# ELEKTRA-PMIC_v0_4-35X22_86.net
KiCad netlist of a schematic drawn in EAGLE
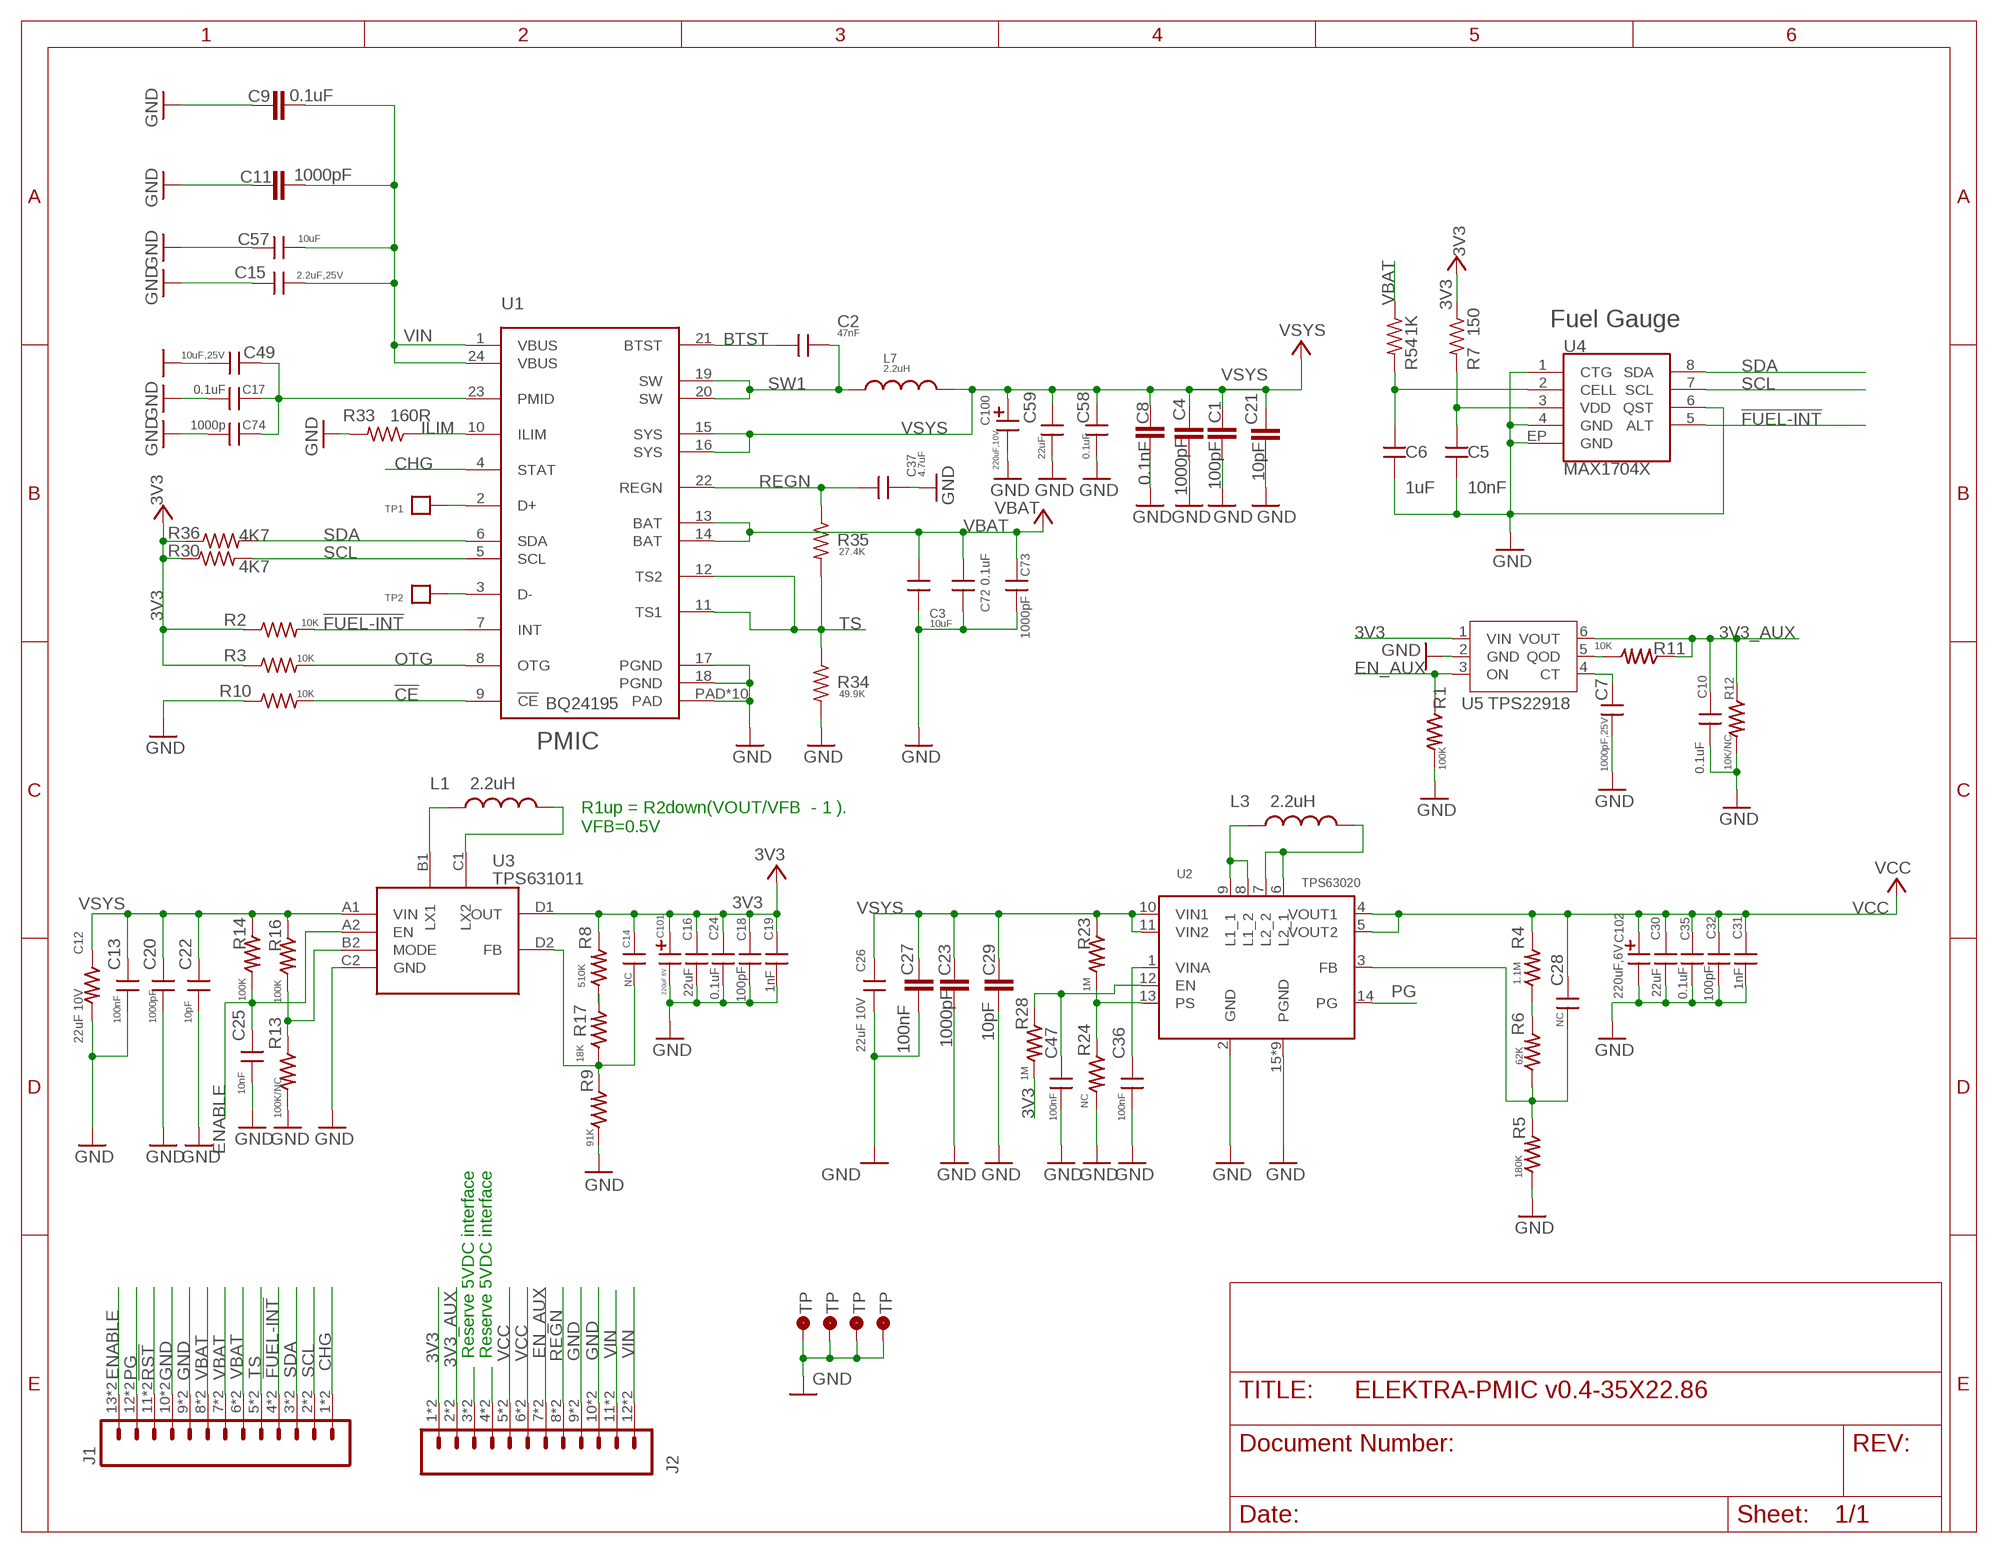
[diagram p0: schematic, sheet 1]

(export (version "E")
  (design (tool "Eeschema 10.0.6"))
  (components
    (comp (ref "C1")
      (value "100pF")
      (footprint "eagle-import:C0402_B")
      (libsource (lib "eagle-import") (part "CAP_1"))
    )
    (comp (ref "C2")
      (value "47nF")
      (footprint "eagle-import:C-0402")
      (libsource (lib "eagle-import") (part "particle SZ_CAP0402"))
    )
    (comp (ref "C3")
      (value "10uF")
      (footprint "eagle-import:C0805")
      (libsource (lib "eagle-import") (part "particle SZ_CAPC0805"))
    )
    (comp (ref "C4")
      (value "1000pF")
      (footprint "eagle-import:C0402_B")
      (libsource (lib "eagle-import") (part "CAP_1"))
    )
    (comp (ref "C5")
      (value "10nF")
      (footprint "eagle-import:C0402")
      (libsource (lib "eagle-import") (part "particle SZ_CAP0402A"))
    )
    (comp (ref "C6")
      (value "1uF")
      (footprint "eagle-import:C0402")
      (libsource (lib "eagle-import") (part "particle SZ_CAP0402A"))
    )
    (comp (ref "C7")
      (value "1000pF,25V")
      (footprint "eagle-import:C0402")
      (libsource (lib "eagle-import") (part "particle SZ_CAP0402A"))
    )
    (comp (ref "C8")
      (value "0.1nF")
      (footprint "eagle-import:C0402_B")
      (libsource (lib "eagle-import") (part "CAP_1"))
    )
    (comp (ref "C9")
      (value "0.1uF")
      (footprint "eagle-import:C0402_B")
      (libsource (lib "eagle-import") (part "CAP_1"))
    )
    (comp (ref "C10")
      (value "0.1uF")
      (footprint "eagle-import:C0201-N")
      (libsource (lib "eagle-import") (part "CAPC0201-N"))
    )
    (comp (ref "C11")
      (value "1000pF")
      (footprint "eagle-import:C0402_B")
      (libsource (lib "eagle-import") (part "CAP_1"))
    )
    (comp (ref "C12")
      (value "22uF 10V")
      (footprint "eagle-import:R-0603A")
      (libsource (lib "eagle-import") (part "RESR0603A"))
    )
    (comp (ref "C13")
      (value "100nF")
      (footprint "eagle-import:C0201-N")
      (libsource (lib "eagle-import") (part "CAPC0201-N"))
    )
    (comp (ref "C14")
      (value "NC")
      (footprint "eagle-import:C0201-N")
      (libsource (lib "eagle-import") (part "CAPC0201-N"))
    )
    (comp (ref "C15")
      (value "2.2uF,25V")
      (footprint "eagle-import:C-0603A")
      (libsource (lib "eagle-import") (part "particle SZ_CAP0603A"))
    )
    (comp (ref "C16")
      (value "22uF")
      (footprint "eagle-import:C-0603A")
      (libsource (lib "eagle-import") (part "particle SZ_21650216_CAP0603A"))
    )
    (comp (ref "C17")
      (value "0.1uF")
      (footprint "eagle-import:C0402")
      (libsource (lib "eagle-import") (part "CAP0402A"))
    )
    (comp (ref "C18")
      (value "100pF")
      (footprint "eagle-import:C0402")
      (libsource (lib "eagle-import") (part "particle SZ_CAP0402A"))
    )
    (comp (ref "C19")
      (value "1nF")
      (footprint "eagle-import:C0402")
      (libsource (lib "eagle-import") (part "particle SZ_CAP0402A"))
    )
    (comp (ref "C20")
      (value "1000pF")
      (footprint "eagle-import:C0201-N")
      (libsource (lib "eagle-import") (part "CAPC0201-N"))
    )
    (comp (ref "C21")
      (value "10pF")
      (footprint "eagle-import:C0402_B")
      (libsource (lib "eagle-import") (part "CAP_1"))
    )
    (comp (ref "C22")
      (value "10pF")
      (footprint "eagle-import:C0201-N")
      (libsource (lib "eagle-import") (part "CAPC0201-N"))
    )
    (comp (ref "C23")
      (value "1000pF")
      (footprint "eagle-import:C0402_B")
      (libsource (lib "eagle-import") (part "CAP_1"))
    )
    (comp (ref "C24")
      (value "0.1uF")
      (footprint "eagle-import:C0402")
      (libsource (lib "eagle-import") (part "particle SZ_CAP0402A"))
    )
    (comp (ref "C25")
      (value "10nF")
      (footprint "eagle-import:C0201-N")
      (libsource (lib "eagle-import") (part "CAPC0201-N"))
    )
    (comp (ref "C26")
      (value "22uF 10V")
      (footprint "eagle-import:C0603")
      (libsource (lib "eagle-import") (part "particle SZ_21650216_CAPC0603"))
    )
    (comp (ref "C27")
      (value "100nF")
      (footprint "eagle-import:C0402_B")
      (libsource (lib "eagle-import") (part "CAP_1"))
    )
    (comp (ref "C28")
      (value "NC")
      (footprint "eagle-import:C0201-N")
      (libsource (lib "eagle-import") (part "CAPC0201-N"))
    )
    (comp (ref "C29")
      (value "10pF")
      (footprint "eagle-import:C0402_B")
      (libsource (lib "eagle-import") (part "CAP_1"))
    )
    (comp (ref "C30")
      (value "22uF")
      (footprint "eagle-import:C-0603A")
      (libsource (lib "eagle-import") (part "particle SZ_21650216_CAP0603A"))
    )
    (comp (ref "C31")
      (value "1nF")
      (footprint "eagle-import:C0402")
      (libsource (lib "eagle-import") (part "particle SZ_CAP0402A"))
    )
    (comp (ref "C32")
      (value "100pF")
      (footprint "eagle-import:C0402")
      (libsource (lib "eagle-import") (part "particle SZ_CAP0402A"))
    )
    (comp (ref "C35")
      (value "0.1uF")
      (footprint "eagle-import:C0402")
      (libsource (lib "eagle-import") (part "particle SZ_CAP0402A"))
    )
    (comp (ref "C36")
      (value "100nF")
      (footprint "eagle-import:C0201-N")
      (libsource (lib "eagle-import") (part "CAPC0201-N"))
    )
    (comp (ref "C37")
      (value "4.7uF")
      (footprint "eagle-import:C0402")
      (libsource (lib "eagle-import") (part "particle SZ_CAP0402A"))
    )
    (comp (ref "C47")
      (value "100nF")
      (footprint "eagle-import:C0201-N")
      (libsource (lib "eagle-import") (part "CAPC0201-N"))
    )
    (comp (ref "C49")
      (value "10uF,25V")
      (footprint "eagle-import:C-0603A")
      (libsource (lib "eagle-import") (part "particle SZ_CAP0603A"))
    )
    (comp (ref "C57")
      (value "10uF")
      (footprint "eagle-import:C-0603A")
      (libsource (lib "eagle-import") (part "particle SZ_CAP0603A"))
    )
    (comp (ref "C58")
      (value "0.1uF")
      (footprint "eagle-import:C0402")
      (libsource (lib "eagle-import") (part "particle SZ_CAP0402A"))
    )
    (comp (ref "C59")
      (value "22uF")
      (footprint "eagle-import:C0603")
      (libsource (lib "eagle-import") (part "particle SZ_CAPC0603"))
    )
    (comp (ref "C72")
      (value "0.1uF")
      (footprint "eagle-import:C-0402")
      (libsource (lib "eagle-import") (part "particle SZ_CAP0402"))
    )
    (comp (ref "C73")
      (value "1000pF")
      (footprint "eagle-import:C-0402")
      (libsource (lib "eagle-import") (part "particle SZ_CAP0402"))
    )
    (comp (ref "C74")
      (value "1000p")
      (footprint "eagle-import:C-0402")
      (libsource (lib "eagle-import") (part "particle SZ_CAP0402"))
    )
    (comp (ref "C100")
      (value "220uF,10V")
      (footprint "eagle-import:CASE-B")
      (libsource (lib "eagle-import") (part "CAP-ECASE_B"))
    )
    (comp (ref "C101")
      (value "220uF.6V")
      (footprint "eagle-import:CASE-B")
      (libsource (lib "eagle-import") (part "CAP-ECASE_B"))
    )
    (comp (ref "C102")
      (value "220uF,6V")
      (footprint "eagle-import:CASE-B")
      (libsource (lib "eagle-import") (part "CAP-ECASE_B"))
    )
    (comp (ref "J1")
      (value "M13PTH-CST-R")
      (footprint "eagle-import:1X13-CASTELLATED")
      (libsource (lib "eagle-import") (part "M13PTH-CST-R"))
    )
    (comp (ref "J2")
      (value "M12PTH-CST-R")
      (footprint "eagle-import:1X12-CASTELLATED")
      (libsource (lib "eagle-import") (part "M12PTH-CST-R"))
    )
    (comp (ref "L1")
      (value "2.2uH")
      (footprint "eagle-import:INDUCTOR-2520")
      (libsource (lib "eagle-import") (part "INDUCTOR-SPARKFUNINDUCTOR-2520"))
    )
    (comp (ref "L3")
      (value "2.2uH")
      (footprint "eagle-import:INDUCTOR-2520")
      (libsource (lib "eagle-import") (part "INDUCTOR-SPARKFUNINDUCTOR-2520"))
    )
    (comp (ref "L7")
      (value "2.2uH")
      (footprint "eagle-import:INDUCTOR-4040")
      (libsource (lib "eagle-import") (part "INDUCTORI"))
    )
    (comp (ref "R1")
      (value "100K")
      (footprint "eagle-import:R0201-N")
      (libsource (lib "eagle-import") (part "RESR0201-N"))
    )
    (comp (ref "R2")
      (value "10K")
      (footprint "eagle-import:R0402_B")
      (libsource (lib "eagle-import") (part "Spark_R-US_"))
    )
    (comp (ref "R3")
      (value "10K")
      (footprint "eagle-import:R0402_B")
      (libsource (lib "eagle-import") (part "Spark_R-US_"))
    )
    (comp (ref "R4")
      (value "1.1M")
      (footprint "eagle-import:R0201-N")
      (libsource (lib "eagle-import") (part "RESR0201-N"))
    )
    (comp (ref "R5")
      (value "180K")
      (footprint "eagle-import:R0201-N")
      (libsource (lib "eagle-import") (part "RESR0201-N"))
    )
    (comp (ref "R6")
      (value "62K")
      (footprint "eagle-import:R0201-N")
      (libsource (lib "eagle-import") (part "RESR0201-N"))
    )
    (comp (ref "R7")
      (value "150")
      (footprint "eagle-import:R0402_B")
      (libsource (lib "eagle-import") (part "R-US_"))
    )
    (comp (ref "R8")
      (value "510K")
      (footprint "eagle-import:R0201-N")
      (libsource (lib "eagle-import") (part "RESR0201-N"))
    )
    (comp (ref "R9")
      (value "91K")
      (footprint "eagle-import:R0201-N")
      (libsource (lib "eagle-import") (part "RESR0201-N"))
    )
    (comp (ref "R10")
      (value "10K")
      (footprint "eagle-import:R0402_B")
      (libsource (lib "eagle-import") (part "Spark_R-US_"))
    )
    (comp (ref "R11")
      (value "10K")
      (footprint "eagle-import:R0201-N")
      (libsource (lib "eagle-import") (part "RESR0201-N"))
    )
    (comp (ref "R12")
      (value "10K/NC")
      (footprint "eagle-import:R0201-N")
      (libsource (lib "eagle-import") (part "RESR0201-N"))
    )
    (comp (ref "R13")
      (value "100K/NC")
      (footprint "eagle-import:R0201-N")
      (libsource (lib "eagle-import") (part "RESR0201-N"))
    )
    (comp (ref "R14")
      (value "100K")
      (footprint "eagle-import:R0201-N")
      (libsource (lib "eagle-import") (part "RESR0201-N"))
    )
    (comp (ref "R16")
      (value "100K")
      (footprint "eagle-import:R0201-N")
      (libsource (lib "eagle-import") (part "RESR0201-N"))
    )
    (comp (ref "R17")
      (value "18K")
      (footprint "eagle-import:R0201-N")
      (libsource (lib "eagle-import") (part "RESR0201-N"))
    )
    (comp (ref "R23")
      (value "1M")
      (footprint "eagle-import:R0201-N")
      (libsource (lib "eagle-import") (part "RESR0201-N"))
    )
    (comp (ref "R24")
      (value "NC")
      (footprint "eagle-import:R0201-N")
      (libsource (lib "eagle-import") (part "RESR0201-N"))
    )
    (comp (ref "R28")
      (value "1M")
      (footprint "eagle-import:R0201-N")
      (libsource (lib "eagle-import") (part "RESR0201-N"))
    )
    (comp (ref "R30")
      (value "4K7")
      (footprint "eagle-import:R0402_B")
      (libsource (lib "eagle-import") (part "R-US_"))
    )
    (comp (ref "R33")
      (value "160R")
      (footprint "eagle-import:R0402_B")
      (libsource (lib "eagle-import") (part "R-US_"))
    )
    (comp (ref "R34")
      (value "49.9K")
      (footprint "eagle-import:R0402_B")
      (libsource (lib "eagle-import") (part "Spark_R-US_"))
    )
    (comp (ref "R35")
      (value "27.4K")
      (footprint "eagle-import:R0402_B")
      (libsource (lib "eagle-import") (part "Spark_R-US_"))
    )
    (comp (ref "R36")
      (value "4K7")
      (footprint "eagle-import:R0402_B")
      (libsource (lib "eagle-import") (part "R-US_"))
    )
    (comp (ref "R54")
      (value "1K")
      (footprint "eagle-import:R0402_B")
      (libsource (lib "eagle-import") (part "R-US_"))
    )
    (comp (ref "TP1")
      (value "TP1311MM")
      (footprint "eagle-import:TP-1311MM")
      (libsource (lib "eagle-import") (part "TP1311MM"))
    )
    (comp (ref "TP2")
      (value "TP1311MM")
      (footprint "eagle-import:TP-1311MM")
      (libsource (lib "eagle-import") (part "TP1311MM"))
    )
    (comp (ref "U$1")
      (value "TP")
      (footprint "eagle-import:TP_2.33X1.37")
      (libsource (lib "eagle-import") (part "TP"))
    )
    (comp (ref "U$2")
      (value "TP")
      (footprint "eagle-import:TP_2.33X1.37")
      (libsource (lib "eagle-import") (part "TP"))
    )
    (comp (ref "U$4")
      (value "TP")
      (footprint "eagle-import:TP_2.33X1.37")
      (libsource (lib "eagle-import") (part "TP"))
    )
    (comp (ref "U$5")
      (value "TP")
      (footprint "eagle-import:TP_2.33X1.37")
      (libsource (lib "eagle-import") (part "TP"))
    )
    (comp (ref "U1")
      (value "BQ24195")
      (footprint "eagle-import:ELECTRON_QFN24")
      (libsource (lib "eagle-import") (part "ELECTRON_BQ24298RTWR"))
    )
    (comp (ref "U2")
      (value "TPS63020")
      (footprint "eagle-import:TPS63020")
      (libsource (lib "eagle-import") (part "TPS63020"))
    )
    (comp (ref "U3")
      (value "TPS631011")
      (footprint "eagle-import:DSBGA")
      (libsource (lib "eagle-import") (part "TPS631010"))
    )
    (comp (ref "U4")
      (value "MAX1704X")
      (footprint "eagle-import:TDFN-8")
      (libsource (lib "eagle-import") (part "MAX1704X"))
    )
    (comp (ref "U5")
      (value "TPS22918")
      (footprint "eagle-import:SOT-23-6")
      (libsource (lib "eagle-import") (part "TPS22918"))
    )
  )
  (nets
    (net (code "1") (name "/3V3_AUX") (class "Default")
      (node (ref "C10") (pin "1") (pinfunction "1_1") (pintype "bidirectional"))
      (node (ref "J2") (pin "2") (pinfunction "2_2") (pintype "passive"))
      (node (ref "J2") (pin "@2") (pinfunction "2_@2") (pintype "passive"))
      (node (ref "R11") (pin "1") (pinfunction "1_1") (pintype "bidirectional"))
      (node (ref "R12") (pin "1") (pinfunction "1_1") (pintype "bidirectional"))
      (node (ref "U5") (pin "6") (pinfunction "VOUT_6") (pintype "bidirectional"))
    )
    (net (code "2") (name "/BTST") (class "Default")
      (node (ref "C2") (pin "1") (pinfunction "1_1") (pintype "bidirectional"))
      (node (ref "U1") (pin "21") (pinfunction "BTST_21") (pintype "bidirectional"))
    )
    (net (code "3") (name "/CHG") (class "Default")
      (node (ref "J1") (pin "1") (pinfunction "1_1") (pintype "passive"))
      (node (ref "J1") (pin "@1") (pinfunction "1_@1") (pintype "passive"))
      (node (ref "U1") (pin "4") (pinfunction "STAT_4") (pintype "bidirectional"))
    )
    (net (code "4") (name "/ENABLE") (class "Default")
      (node (ref "C25") (pin "1") (pinfunction "1_1") (pintype "bidirectional"))
      (node (ref "J1") (pin "13") (pinfunction "13_13") (pintype "passive"))
      (node (ref "J1") (pin "@13") (pinfunction "13_@13") (pintype "passive"))
      (node (ref "R14") (pin "2") (pinfunction "2_2") (pintype "bidirectional"))
      (node (ref "U3") (pin "A2") (pinfunction "EN_A2") (pintype "bidirectional"))
    )
    (net (code "5") (name "/EN_AUX") (class "Default")
      (node (ref "J2") (pin "7") (pinfunction "7_7") (pintype "passive"))
      (node (ref "J2") (pin "@7") (pinfunction "7_@7") (pintype "passive"))
      (node (ref "R1") (pin "1") (pinfunction "1_1") (pintype "bidirectional"))
      (node (ref "U5") (pin "3") (pinfunction "ON_3") (pintype "bidirectional"))
    )
    (net (code "6") (name "/ILIM") (class "Default")
      (node (ref "R33") (pin "1") (pinfunction "1_1") (pintype "passive"))
      (node (ref "U1") (pin "10") (pinfunction "ILIM_10") (pintype "output"))
    )
    (net (code "7") (name "/OTG") (class "Default")
      (node (ref "R3") (pin "2") (pinfunction "2_2") (pintype "passive"))
      (node (ref "U1") (pin "8") (pinfunction "OTG_8") (pintype "bidirectional"))
    )
    (net (code "8") (name "/PG") (class "Default")
      (node (ref "J1") (pin "12") (pinfunction "12_12") (pintype "passive"))
      (node (ref "J1") (pin "@12") (pinfunction "12_@12") (pintype "passive"))
      (node (ref "U2") (pin "14") (pinfunction "PG_14") (pintype "bidirectional"))
    )
    (net (code "9") (name "/REGN") (class "Default")
      (node (ref "C37") (pin "1") (pinfunction "1_1") (pintype "bidirectional"))
      (node (ref "J2") (pin "8") (pinfunction "8_8") (pintype "passive"))
      (node (ref "J2") (pin "@8") (pinfunction "8_@8") (pintype "passive"))
      (node (ref "R35") (pin "1") (pinfunction "1_1") (pintype "passive"))
      (node (ref "U1") (pin "22") (pinfunction "REGN_22") (pintype "bidirectional"))
    )
    (net (code "10") (name "/SCL") (class "Default")
      (node (ref "J1") (pin "2") (pinfunction "2_2") (pintype "passive"))
      (node (ref "J1") (pin "@2") (pinfunction "2_@2") (pintype "passive"))
      (node (ref "R30") (pin "2") (pinfunction "2_2") (pintype "passive"))
      (node (ref "U1") (pin "5") (pinfunction "SCL_5") (pintype "output"))
      (node (ref "U4") (pin "7") (pinfunction "SCL_7") (pintype "bidirectional"))
    )
    (net (code "11") (name "/SDA") (class "Default")
      (node (ref "J1") (pin "3") (pinfunction "3_3") (pintype "passive"))
      (node (ref "J1") (pin "@3") (pinfunction "3_@3") (pintype "passive"))
      (node (ref "R36") (pin "2") (pinfunction "2_2") (pintype "passive"))
      (node (ref "U1") (pin "6") (pinfunction "SDA_6") (pintype "bidirectional"))
      (node (ref "U4") (pin "8") (pinfunction "SDA_8") (pintype "bidirectional"))
    )
    (net (code "12") (name "/SW1") (class "Default")
      (node (ref "C2") (pin "2") (pinfunction "2_2") (pintype "bidirectional"))
      (node (ref "L7") (pin "P$1") (pinfunction "1_P$1") (pintype "passive"))
      (node (ref "U1") (pin "19") (pinfunction "SW_19") (pintype "power_in"))
      (node (ref "U1") (pin "20") (pinfunction "SW_20") (pintype "power_in"))
    )
    (net (code "13") (name "/TS") (class "Default")
      (node (ref "J1") (pin "5") (pinfunction "5_5") (pintype "passive"))
      (node (ref "J1") (pin "@5") (pinfunction "5_@5") (pintype "passive"))
      (node (ref "R34") (pin "1") (pinfunction "1_1") (pintype "passive"))
      (node (ref "R35") (pin "2") (pinfunction "2_2") (pintype "passive"))
      (node (ref "U1") (pin "11") (pinfunction "TS1_11") (pintype "bidirectional"))
      (node (ref "U1") (pin "12") (pinfunction "TS2_12") (pintype "bidirectional"))
    )
    (net (code "14") (name "/VIN") (class "Default")
      (node (ref "C11") (pin "2") (pinfunction "P$2_2") (pintype "passive"))
      (node (ref "C15") (pin "1") (pinfunction "1_1") (pintype "bidirectional"))
      (node (ref "C57") (pin "1") (pinfunction "1_1") (pintype "bidirectional"))
      (node (ref "C9") (pin "2") (pinfunction "P$2_2") (pintype "passive"))
      (node (ref "J2") (pin "11") (pinfunction "11_11") (pintype "passive"))
      (node (ref "J2") (pin "12") (pinfunction "12_12") (pintype "passive"))
      (node (ref "J2") (pin "@11") (pinfunction "11_@11") (pintype "passive"))
      (node (ref "J2") (pin "@12") (pinfunction "12_@12") (pintype "passive"))
      (node (ref "U1") (pin "1") (pinfunction "VBUS_1") (pintype "power_in"))
      (node (ref "U1") (pin "24") (pinfunction "VBUS_24") (pintype "passive"))
    )
    (net (code "15") (name "/~{CE}") (class "Default")
      (node (ref "R10") (pin "2") (pinfunction "2_2") (pintype "passive"))
      (node (ref "U1") (pin "9") (pinfunction "~{CE}_9") (pintype "output"))
    )
    (net (code "16") (name "/~{FUEL-INT}") (class "Default")
      (node (ref "J1") (pin "4") (pinfunction "4_4") (pintype "passive"))
      (node (ref "J1") (pin "@4") (pinfunction "4_@4") (pintype "passive"))
      (node (ref "R2") (pin "2") (pinfunction "2_2") (pintype "passive"))
      (node (ref "U1") (pin "7") (pinfunction "INT_7") (pintype "bidirectional"))
      (node (ref "U4") (pin "5") (pinfunction "ALT_5") (pintype "bidirectional"))
    )
    (net (code "17") (name "/~{RST}") (class "Default")
      (node (ref "J1") (pin "11") (pinfunction "11_11") (pintype "passive"))
      (node (ref "J1") (pin "@11") (pinfunction "11_@11") (pintype "passive"))
    )
    (net (code "18") (name "3V3") (class "Default")
      (node (ref "C101") (pin "P$1") (pinfunction "1_P$1") (pintype "bidirectional"))
      (node (ref "C14") (pin "1") (pinfunction "1_1") (pintype "bidirectional"))
      (node (ref "C16") (pin "1") (pinfunction "1_1") (pintype "bidirectional"))
      (node (ref "C18") (pin "1") (pinfunction "1_1") (pintype "bidirectional"))
      (node (ref "C19") (pin "1") (pinfunction "1_1") (pintype "bidirectional"))
      (node (ref "C24") (pin "1") (pinfunction "1_1") (pintype "bidirectional"))
      (node (ref "J2") (pin "1") (pinfunction "1_1") (pintype "passive"))
      (node (ref "J2") (pin "@1") (pinfunction "1_@1") (pintype "passive"))
      (node (ref "R2") (pin "1") (pinfunction "1_1") (pintype "passive"))
      (node (ref "R28") (pin "2") (pinfunction "2_2") (pintype "bidirectional"))
      (node (ref "R3") (pin "1") (pinfunction "1_1") (pintype "passive"))
      (node (ref "R30") (pin "1") (pinfunction "1_1") (pintype "passive"))
      (node (ref "R36") (pin "1") (pinfunction "1_1") (pintype "passive"))
      (node (ref "R7") (pin "1") (pinfunction "1_1") (pintype "passive"))
      (node (ref "R8") (pin "2") (pinfunction "2_2") (pintype "bidirectional"))
      (node (ref "U3") (pin "D1") (pinfunction "OUT_D1") (pintype "bidirectional"))
      (node (ref "U5") (pin "1") (pinfunction "VIN_1") (pintype "bidirectional"))
    )
    (net (code "19") (name "GND") (class "Default")
      (node (ref "C1") (pin "1") (pinfunction "P$1_1") (pintype "passive"))
      (node (ref "C10") (pin "2") (pinfunction "2_2") (pintype "bidirectional"))
      (node (ref "C100") (pin "P$2") (pinfunction "2_P$2") (pintype "bidirectional"))
      (node (ref "C101") (pin "P$2") (pinfunction "2_P$2") (pintype "bidirectional"))
      (node (ref "C102") (pin "P$2") (pinfunction "2_P$2") (pintype "bidirectional"))
      (node (ref "C11") (pin "1") (pinfunction "P$1_1") (pintype "passive"))
      (node (ref "C12") (pin "2") (pinfunction "2_2") (pintype "bidirectional"))
      (node (ref "C13") (pin "2") (pinfunction "2_2") (pintype "bidirectional"))
      (node (ref "C15") (pin "2") (pinfunction "2_2") (pintype "bidirectional"))
      (node (ref "C16") (pin "2") (pinfunction "2_2") (pintype "bidirectional"))
      (node (ref "C17") (pin "1") (pinfunction "1_1") (pintype "bidirectional"))
      (node (ref "C18") (pin "2") (pinfunction "2_2") (pintype "bidirectional"))
      (node (ref "C19") (pin "2") (pinfunction "2_2") (pintype "bidirectional"))
      (node (ref "C20") (pin "2") (pinfunction "2_2") (pintype "bidirectional"))
      (node (ref "C21") (pin "1") (pinfunction "P$1_1") (pintype "passive"))
      (node (ref "C22") (pin "2") (pinfunction "2_2") (pintype "bidirectional"))
      (node (ref "C23") (pin "1") (pinfunction "P$1_1") (pintype "passive"))
      (node (ref "C24") (pin "2") (pinfunction "2_2") (pintype "bidirectional"))
      (node (ref "C25") (pin "2") (pinfunction "2_2") (pintype "bidirectional"))
      (node (ref "C26") (pin "2") (pinfunction "2_2") (pintype "bidirectional"))
      (node (ref "C27") (pin "1") (pinfunction "P$1_1") (pintype "passive"))
      (node (ref "C29") (pin "1") (pinfunction "P$1_1") (pintype "passive"))
      (node (ref "C3") (pin "2") (pinfunction "2_2") (pintype "bidirectional"))
      (node (ref "C30") (pin "2") (pinfunction "2_2") (pintype "bidirectional"))
      (node (ref "C31") (pin "2") (pinfunction "2_2") (pintype "bidirectional"))
      (node (ref "C32") (pin "2") (pinfunction "2_2") (pintype "bidirectional"))
      (node (ref "C35") (pin "2") (pinfunction "2_2") (pintype "bidirectional"))
      (node (ref "C36") (pin "2") (pinfunction "2_2") (pintype "bidirectional"))
      (node (ref "C37") (pin "2") (pinfunction "2_2") (pintype "bidirectional"))
      (node (ref "C4") (pin "1") (pinfunction "P$1_1") (pintype "passive"))
      (node (ref "C47") (pin "2") (pinfunction "2_2") (pintype "bidirectional"))
      (node (ref "C49") (pin "2") (pinfunction "2_2") (pintype "bidirectional"))
      (node (ref "C5") (pin "2") (pinfunction "2_2") (pintype "bidirectional"))
      (node (ref "C57") (pin "2") (pinfunction "2_2") (pintype "bidirectional"))
      (node (ref "C58") (pin "2") (pinfunction "2_2") (pintype "bidirectional"))
      (node (ref "C59") (pin "2") (pinfunction "2_2") (pintype "bidirectional"))
      (node (ref "C6") (pin "2") (pinfunction "2_2") (pintype "bidirectional"))
      (node (ref "C7") (pin "2") (pinfunction "2_2") (pintype "bidirectional"))
      (node (ref "C72") (pin "2") (pinfunction "2_2") (pintype "bidirectional"))
      (node (ref "C73") (pin "2") (pinfunction "2_2") (pintype "bidirectional"))
      (node (ref "C74") (pin "1") (pinfunction "1_1") (pintype "bidirectional"))
      (node (ref "C8") (pin "1") (pinfunction "P$1_1") (pintype "passive"))
      (node (ref "C9") (pin "1") (pinfunction "P$1_1") (pintype "passive"))
      (node (ref "J1") (pin "10") (pinfunction "10_10") (pintype "passive"))
      (node (ref "J1") (pin "9") (pinfunction "9_9") (pintype "passive"))
      (node (ref "J1") (pin "@10") (pinfunction "10_@10") (pintype "passive"))
      (node (ref "J1") (pin "@9") (pinfunction "9_@9") (pintype "passive"))
      (node (ref "J2") (pin "10") (pinfunction "10_10") (pintype "passive"))
      (node (ref "J2") (pin "9") (pinfunction "9_9") (pintype "passive"))
      (node (ref "J2") (pin "@10") (pinfunction "10_@10") (pintype "passive"))
      (node (ref "J2") (pin "@9") (pinfunction "9_@9") (pintype "passive"))
      (node (ref "R1") (pin "2") (pinfunction "2_2") (pintype "bidirectional"))
      (node (ref "R10") (pin "1") (pinfunction "1_1") (pintype "passive"))
      (node (ref "R12") (pin "2") (pinfunction "2_2") (pintype "bidirectional"))
      (node (ref "R13") (pin "2") (pinfunction "2_2") (pintype "bidirectional"))
      (node (ref "R24") (pin "2") (pinfunction "2_2") (pintype "bidirectional"))
      (node (ref "R33") (pin "2") (pinfunction "2_2") (pintype "passive"))
      (node (ref "R34") (pin "2") (pinfunction "2_2") (pintype "passive"))
      (node (ref "R5") (pin "1") (pinfunction "1_1") (pintype "bidirectional"))
      (node (ref "R9") (pin "1") (pinfunction "1_1") (pintype "bidirectional"))
      (node (ref "U$1") (pin "1") (pinfunction "TP_1") (pintype "bidirectional"))
      (node (ref "U$2") (pin "1") (pinfunction "TP_1") (pintype "bidirectional"))
      (node (ref "U$4") (pin "1") (pinfunction "TP_1") (pintype "bidirectional"))
      (node (ref "U$5") (pin "1") (pinfunction "TP_1") (pintype "bidirectional"))
      (node (ref "U1") (pin "17") (pinfunction "PGND_17") (pintype "passive"))
      (node (ref "U1") (pin "18") (pinfunction "PGND_18") (pintype "passive"))
      (node (ref "U1") (pin "PAD") (pinfunction "PAD_PAD") (pintype "power_in"))
      (node (ref "U1") (pin "PAD@1") (pinfunction "PAD_PAD@1") (pintype "power_in"))
      (node (ref "U1") (pin "PAD@2") (pinfunction "PAD_PAD@2") (pintype "power_in"))
      (node (ref "U1") (pin "PAD@3") (pinfunction "PAD_PAD@3") (pintype "power_in"))
      (node (ref "U1") (pin "PAD@4") (pinfunction "PAD_PAD@4") (pintype "power_in"))
      (node (ref "U1") (pin "PAD@5") (pinfunction "PAD_PAD@5") (pintype "power_in"))
      (node (ref "U1") (pin "PAD@6") (pinfunction "PAD_PAD@6") (pintype "power_in"))
      (node (ref "U1") (pin "PAD@7") (pinfunction "PAD_PAD@7") (pintype "power_in"))
      (node (ref "U1") (pin "PAD@8") (pinfunction "PAD_PAD@8") (pintype "power_in"))
      (node (ref "U1") (pin "PAD@9") (pinfunction "PAD_PAD@9") (pintype "power_in"))
      (node (ref "U2") (pin "15") (pinfunction "PGND_15") (pintype "bidirectional"))
      (node (ref "U2") (pin "16") (pinfunction "PGND_16") (pintype "bidirectional"))
      (node (ref "U2") (pin "17") (pinfunction "PGND_17") (pintype "bidirectional"))
      (node (ref "U2") (pin "18") (pinfunction "PGND_18") (pintype "bidirectional"))
      (node (ref "U2") (pin "19") (pinfunction "PGND_19") (pintype "bidirectional"))
      (node (ref "U2") (pin "2") (pinfunction "GND_2") (pintype "bidirectional"))
      (node (ref "U2") (pin "20") (pinfunction "PGND_20") (pintype "bidirectional"))
      (node (ref "U2") (pin "21") (pinfunction "PGND_21") (pintype "bidirectional"))
      (node (ref "U2") (pin "22") (pinfunction "PGND_22") (pintype "bidirectional"))
      (node (ref "U2") (pin "23") (pinfunction "PGND_23") (pintype "bidirectional"))
      (node (ref "U3") (pin "C2") (pinfunction "GND_C2") (pintype "bidirectional"))
      (node (ref "U4") (pin "1") (pinfunction "CTG_1") (pintype "bidirectional"))
      (node (ref "U4") (pin "4") (pinfunction "GND_4") (pintype "bidirectional"))
      (node (ref "U4") (pin "6") (pinfunction "QST_6") (pintype "bidirectional"))
      (node (ref "U4") (pin "EP") (pinfunction "GND_EP") (pintype "bidirectional"))
      (node (ref "U5") (pin "2") (pinfunction "GND_2") (pintype "bidirectional"))
    )
    (net (code "20") (name "Net-(J2-3-Pad@3)") (class "Default")
      (node (ref "J2") (pin "3") (pinfunction "3_3") (pintype "passive"))
      (node (ref "J2") (pin "@3") (pinfunction "3_@3") (pintype "passive"))
    )
    (net (code "21") (name "Net-(J2-4-Pad@4)") (class "Default")
      (node (ref "J2") (pin "4") (pinfunction "4_4") (pintype "passive"))
      (node (ref "J2") (pin "@4") (pinfunction "4_@4") (pintype "passive"))
    )
    (net (code "22") (name "Net-(R4-Pad1)") (class "Default")
      (node (ref "R4") (pin "1") (pinfunction "1_1") (pintype "bidirectional"))
      (node (ref "R6") (pin "2") (pinfunction "2_2") (pintype "bidirectional"))
    )
    (net (code "23") (name "Net-(R17-Pad2)") (class "Default")
      (node (ref "R17") (pin "2") (pinfunction "2_2") (pintype "bidirectional"))
      (node (ref "R8") (pin "1") (pinfunction "1_1") (pintype "bidirectional"))
    )
    (net (code "24") (name "Net-(TP1-1)") (class "Default")
      (node (ref "TP1") (pin "P$1") (pinfunction "1_P$1") (pintype "bidirectional"))
      (node (ref "U1") (pin "2") (pinfunction "D+_2") (pintype "output"))
    )
    (net (code "25") (name "Net-(TP2-1)") (class "Default")
      (node (ref "TP2") (pin "P$1") (pinfunction "1_P$1") (pintype "bidirectional"))
      (node (ref "U1") (pin "3") (pinfunction "D-_3") (pintype "output"))
    )
    (net (code "26") (name "Net-(U1-PMID)") (class "Default")
      (node (ref "C17") (pin "2") (pinfunction "2_2") (pintype "bidirectional"))
      (node (ref "C49") (pin "1") (pinfunction "1_1") (pintype "bidirectional"))
      (node (ref "C74") (pin "2") (pinfunction "2_2") (pintype "bidirectional"))
      (node (ref "U1") (pin "23") (pinfunction "PMID_23") (pintype "passive"))
    )
    (net (code "27") (name "Net-(U2-EN)") (class "Default")
      (node (ref "C47") (pin "1") (pinfunction "1_1") (pintype "bidirectional"))
      (node (ref "R28") (pin "1") (pinfunction "1_1") (pintype "bidirectional"))
      (node (ref "U2") (pin "12") (pinfunction "EN_12") (pintype "bidirectional"))
    )
    (net (code "28") (name "Net-(U2-FB)") (class "Default")
      (node (ref "C28") (pin "2") (pinfunction "2_2") (pintype "bidirectional"))
      (node (ref "R5") (pin "2") (pinfunction "2_2") (pintype "bidirectional"))
      (node (ref "R6") (pin "1") (pinfunction "1_1") (pintype "bidirectional"))
      (node (ref "U2") (pin "3") (pinfunction "FB_3") (pintype "bidirectional"))
    )
    (net (code "29") (name "Net-(U2-L1_1)") (class "Default")
      (node (ref "L3") (pin "1") (pinfunction "1_1") (pintype "passive"))
      (node (ref "U2") (pin "8") (pinfunction "L1_2_8") (pintype "bidirectional"))
      (node (ref "U2") (pin "9") (pinfunction "L1_1_9") (pintype "bidirectional"))
    )
    (net (code "30") (name "Net-(U2-L2_1)") (class "Default")
      (node (ref "L3") (pin "2") (pinfunction "2_2") (pintype "passive"))
      (node (ref "U2") (pin "6") (pinfunction "L2_1_6") (pintype "bidirectional"))
      (node (ref "U2") (pin "7") (pinfunction "L2_2_7") (pintype "bidirectional"))
    )
    (net (code "31") (name "Net-(U2-PS)") (class "Default")
      (node (ref "R23") (pin "2") (pinfunction "2_2") (pintype "bidirectional"))
      (node (ref "R24") (pin "1") (pinfunction "1_1") (pintype "bidirectional"))
      (node (ref "U2") (pin "13") (pinfunction "PS_13") (pintype "bidirectional"))
    )
    (net (code "32") (name "Net-(U2-VINA)") (class "Default")
      (node (ref "C36") (pin "1") (pinfunction "1_1") (pintype "bidirectional"))
      (node (ref "U2") (pin "1") (pinfunction "VINA_1") (pintype "bidirectional"))
    )
    (net (code "33") (name "Net-(U3-FB)") (class "Default")
      (node (ref "C14") (pin "2") (pinfunction "2_2") (pintype "bidirectional"))
      (node (ref "R17") (pin "1") (pinfunction "1_1") (pintype "bidirectional"))
      (node (ref "R9") (pin "2") (pinfunction "2_2") (pintype "bidirectional"))
      (node (ref "U3") (pin "D2") (pinfunction "FB_D2") (pintype "bidirectional"))
    )
    (net (code "34") (name "Net-(U3-LX1)") (class "Default")
      (node (ref "L1") (pin "1") (pinfunction "1_1") (pintype "passive"))
      (node (ref "U3") (pin "B1") (pinfunction "LX1_B1") (pintype "bidirectional"))
    )
    (net (code "35") (name "Net-(U3-LX2)") (class "Default")
      (node (ref "L1") (pin "2") (pinfunction "2_2") (pintype "passive"))
      (node (ref "U3") (pin "C1") (pinfunction "LX2_C1") (pintype "bidirectional"))
    )
    (net (code "36") (name "Net-(U3-MODE)") (class "Default")
      (node (ref "R13") (pin "1") (pinfunction "1_1") (pintype "bidirectional"))
      (node (ref "R16") (pin "2") (pinfunction "2_2") (pintype "bidirectional"))
      (node (ref "U3") (pin "B2") (pinfunction "MODE_B2") (pintype "bidirectional"))
    )
    (net (code "37") (name "Net-(U4-CELL)") (class "Default")
      (node (ref "C6") (pin "1") (pinfunction "1_1") (pintype "bidirectional"))
      (node (ref "R54") (pin "2") (pinfunction "2_2") (pintype "passive"))
      (node (ref "U4") (pin "2") (pinfunction "CELL_2") (pintype "bidirectional"))
    )
    (net (code "38") (name "Net-(U4-VDD)") (class "Default")
      (node (ref "C5") (pin "1") (pinfunction "1_1") (pintype "bidirectional"))
      (node (ref "R7") (pin "2") (pinfunction "2_2") (pintype "passive"))
      (node (ref "U4") (pin "3") (pinfunction "VDD_3") (pintype "bidirectional"))
    )
    (net (code "39") (name "Net-(U5-CT)") (class "Default")
      (node (ref "C7") (pin "1") (pinfunction "1_1") (pintype "bidirectional"))
      (node (ref "U5") (pin "4") (pinfunction "CT_4") (pintype "bidirectional"))
    )
    (net (code "40") (name "Net-(U5-QOD)") (class "Default")
      (node (ref "R11") (pin "2") (pinfunction "2_2") (pintype "bidirectional"))
      (node (ref "U5") (pin "5") (pinfunction "QOD_5") (pintype "bidirectional"))
    )
    (net (code "41") (name "VBAT") (class "Default")
      (node (ref "C3") (pin "1") (pinfunction "1_1") (pintype "bidirectional"))
      (node (ref "C72") (pin "1") (pinfunction "1_1") (pintype "bidirectional"))
      (node (ref "C73") (pin "1") (pinfunction "1_1") (pintype "bidirectional"))
      (node (ref "J1") (pin "6") (pinfunction "6_6") (pintype "passive"))
      (node (ref "J1") (pin "7") (pinfunction "7_7") (pintype "passive"))
      (node (ref "J1") (pin "8") (pinfunction "8_8") (pintype "passive"))
      (node (ref "J1") (pin "@6") (pinfunction "6_@6") (pintype "passive"))
      (node (ref "J1") (pin "@7") (pinfunction "7_@7") (pintype "passive"))
      (node (ref "J1") (pin "@8") (pinfunction "8_@8") (pintype "passive"))
      (node (ref "R54") (pin "1") (pinfunction "1_1") (pintype "passive"))
      (node (ref "U1") (pin "13") (pinfunction "BAT_13") (pintype "passive"))
      (node (ref "U1") (pin "14") (pinfunction "BAT_14") (pintype "power_in"))
    )
    (net (code "42") (name "VCC") (class "Default")
      (node (ref "C102") (pin "P$1") (pinfunction "1_P$1") (pintype "bidirectional"))
      (node (ref "C28") (pin "1") (pinfunction "1_1") (pintype "bidirectional"))
      (node (ref "C30") (pin "1") (pinfunction "1_1") (pintype "bidirectional"))
      (node (ref "C31") (pin "1") (pinfunction "1_1") (pintype "bidirectional"))
      (node (ref "C32") (pin "1") (pinfunction "1_1") (pintype "bidirectional"))
      (node (ref "C35") (pin "1") (pinfunction "1_1") (pintype "bidirectional"))
      (node (ref "J2") (pin "5") (pinfunction "5_5") (pintype "passive"))
      (node (ref "J2") (pin "6") (pinfunction "6_6") (pintype "passive"))
      (node (ref "J2") (pin "@5") (pinfunction "5_@5") (pintype "passive"))
      (node (ref "J2") (pin "@6") (pinfunction "6_@6") (pintype "passive"))
      (node (ref "R4") (pin "2") (pinfunction "2_2") (pintype "bidirectional"))
      (node (ref "U2") (pin "4") (pinfunction "VOUT1_4") (pintype "bidirectional"))
      (node (ref "U2") (pin "5") (pinfunction "VOUT2_5") (pintype "bidirectional"))
    )
    (net (code "43") (name "VSYS") (class "Default")
      (node (ref "C1") (pin "2") (pinfunction "P$2_2") (pintype "passive"))
      (node (ref "C100") (pin "P$1") (pinfunction "1_P$1") (pintype "bidirectional"))
      (node (ref "C12") (pin "1") (pinfunction "1_1") (pintype "bidirectional"))
      (node (ref "C13") (pin "1") (pinfunction "1_1") (pintype "bidirectional"))
      (node (ref "C20") (pin "1") (pinfunction "1_1") (pintype "bidirectional"))
      (node (ref "C21") (pin "2") (pinfunction "P$2_2") (pintype "passive"))
      (node (ref "C22") (pin "1") (pinfunction "1_1") (pintype "bidirectional"))
      (node (ref "C23") (pin "2") (pinfunction "P$2_2") (pintype "passive"))
      (node (ref "C26") (pin "1") (pinfunction "1_1") (pintype "bidirectional"))
      (node (ref "C27") (pin "2") (pinfunction "P$2_2") (pintype "passive"))
      (node (ref "C29") (pin "2") (pinfunction "P$2_2") (pintype "passive"))
      (node (ref "C4") (pin "2") (pinfunction "P$2_2") (pintype "passive"))
      (node (ref "C58") (pin "1") (pinfunction "1_1") (pintype "bidirectional"))
      (node (ref "C59") (pin "1") (pinfunction "1_1") (pintype "bidirectional"))
      (node (ref "C8") (pin "2") (pinfunction "P$2_2") (pintype "passive"))
      (node (ref "L7") (pin "P$2") (pinfunction "2_P$2") (pintype "passive"))
      (node (ref "R14") (pin "1") (pinfunction "1_1") (pintype "bidirectional"))
      (node (ref "R16") (pin "1") (pinfunction "1_1") (pintype "bidirectional"))
      (node (ref "R23") (pin "1") (pinfunction "1_1") (pintype "bidirectional"))
      (node (ref "U1") (pin "15") (pinfunction "SYS_15") (pintype "power_in"))
      (node (ref "U1") (pin "16") (pinfunction "SYS_16") (pintype "power_in"))
      (node (ref "U2") (pin "10") (pinfunction "VIN1_10") (pintype "bidirectional"))
      (node (ref "U2") (pin "11") (pinfunction "VIN2_11") (pintype "bidirectional"))
      (node (ref "U3") (pin "A1") (pinfunction "VIN_A1") (pintype "bidirectional"))
    )
  )
)
